# 25D_KernelPeriod_test.net
KiCad netlist of a schematic drawn in Altium Designer
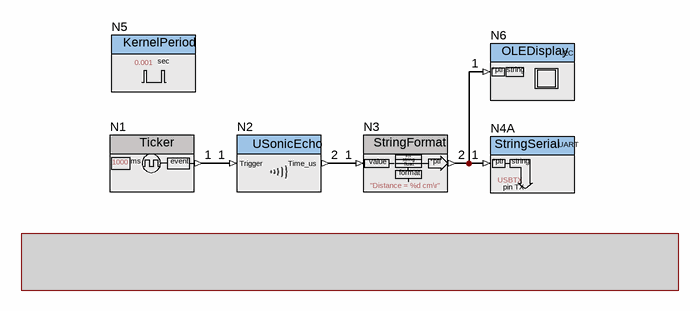
[diagram p0: 25D_KernelPeriod_test.SchDoc]

(export (version "E")
  (design (tool "Eeschema 10.0.6"))
  (components
    (comp (ref "N1")
      (value "Ticker")
      (description "Creates a Periodical Event")
      (fields (field (name "NBLOCKSPARAMETER1") "1000"))
      (libsource (lib "studio") (part "NODE-TICKER"))
    )
    (comp (ref "N2") (value "USonicEcho") (libsource (lib "studio") (part "NODE-USonicEcho")))
    (comp (ref "N3")
      (value "StringFormat")
      (fields (field (name "NBLOCKSPARAMETER1") "\"Distance = %d c~{m}r\""))
      (libsource (lib "studio") (part "NODE-STRINGFORMAT"))
    )
    (comp (ref "N4")
      (value "StringSerial")
      (fields (field (name "NBLOCKSPARAMETER1") "USBTX"))
      (libsource (lib "studio") (part "NODE-STRINGSERIAL-split"))
    )
    (comp (ref "N5")
      (value "KernelPeriod")
      (fields (field (name "NBLOCKSPARAMETER1") "0.001"))
      (libsource (lib "studio") (part "NODE-KernelPeriod"))
    )
    (comp (ref "N6") (value "OLEDisplay") (libsource (lib "studio") (part "NODE-OLEDisplay")))
  )
  (nets
    (net (code "1") (name "Net-(N1-OUT)") (class "Default")
      (node (ref "N1") (pin "1") (pinfunction "OUT_1") (pintype "output"))
      (node (ref "N2") (pin "1") (pinfunction "Trigger_1") (pintype "input"))
    )
    (net (code "2") (name "Net-(N2-Time_us)") (class "Default")
      (node (ref "N2") (pin "2") (pinfunction "Time_us_2") (pintype "output"))
      (node (ref "N3") (pin "1") (pinfunction "IN_1") (pintype "input"))
    )
    (net (code "3") (name "Net-(N3-OUT)") (class "Default")
      (node (ref "N3") (pin "2") (pinfunction "OUT_2") (pintype "output"))
      (node (ref "N4") (pin "1") (pinfunction "TX_1") (pintype "input"))
      (node (ref "N6") (pin "1") (pinfunction "value_1") (pintype "input"))
    )
  )
)
